# Schematic.net
KiCad netlist of a schematic drawn in Altium Designer
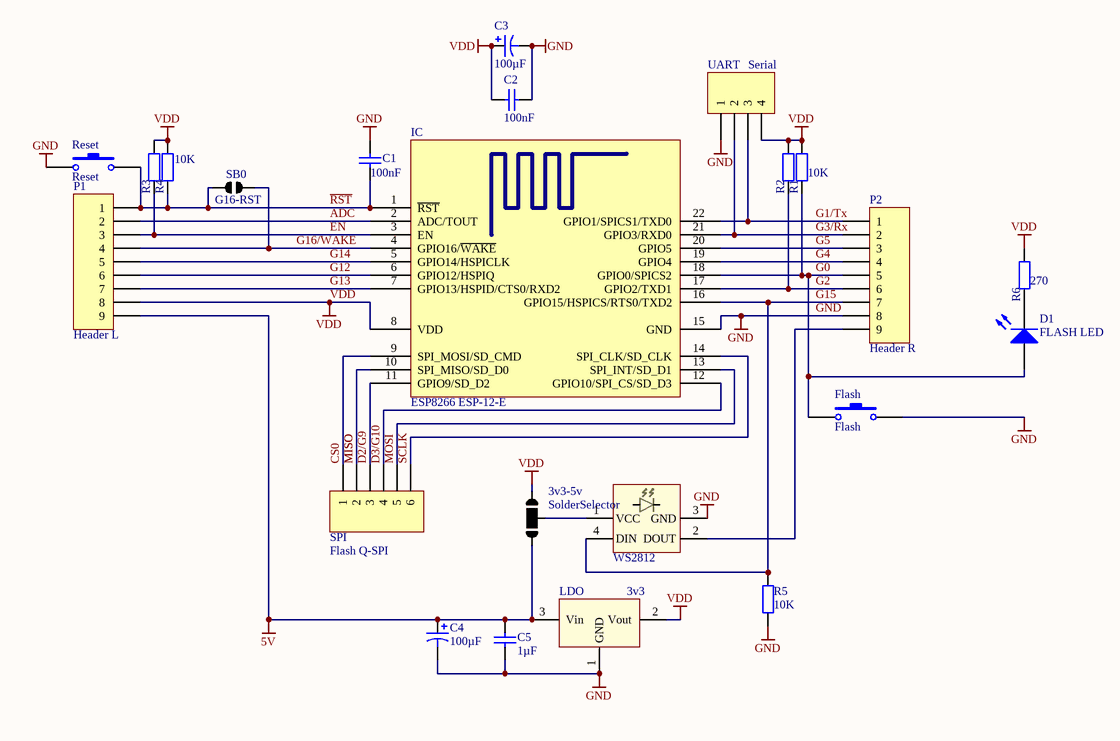
[diagram p0: Schematic.SchDoc]

(export (version "E")
  (design (tool "Eeschema 10.0.6"))
  (components
    (comp (ref "3v3-5v")
      (value "SolderSelector")
      (footprint "SolderSelector")
      (libsource (lib "Misc") (part "SolderSelector"))
    )
    (comp (ref "C1")
      (value "100nF")
      (footprint "C1206")
      (description "Capacitor (Semiconductor SIM Model)")
      (fields (field (name "Comment") "Cap Semi") (field (name "PUBLISHER") "Altium Limited"))
      (libsource (lib "Miscellaneous Devices") (part "Cap Semi"))
    )
    (comp (ref "C2")
      (value "100nF")
      (footprint "C1206")
      (description "Capacitor (Semiconductor SIM Model)")
      (fields (field (name "Comment") "Cap Semi") (field (name "PUBLISHER") "Altium Limited"))
      (libsource (lib "Miscellaneous Devices") (part "Cap Semi"))
    )
    (comp (ref "C3")
      (value "100µF")
      (footprint "SMD cap 6x5")
      (description "Polarized Capacitor (Radial)")
      (fields (field (name "PUBLISHER") "Altium Limited"))
      (libsource (lib "Miscellaneous Devices") (part "Cap Pol1"))
    )
    (comp (ref "C4")
      (value "100µF")
      (footprint "SMD cap 6x5")
      (description "Polarized Capacitor (Radial)")
      (fields (field (name "PUBLISHER") "Altium Limited"))
      (libsource (lib "Miscellaneous Devices") (part "Cap Pol1"))
    )
    (comp (ref "C5")
      (value "1µF")
      (footprint "C1206")
      (description "Capacitor")
      (fields (field (name "PUBLISHER") "Altium Limited"))
      (libsource (lib "Miscellaneous Devices") (part "Cap"))
    )
    (comp (ref "D1")
      (value "FLASH LED")
      (footprint "C1206")
      (description "Typical RED, GREEN, YELLOW, AMBER GaAs LED")
      (fields (field (name "PUBLISHER") "Altium Limited"))
      (libsource (lib "Miscellaneous Devices") (part "LED2"))
    )
    (comp (ref "Flash")
      (value "Flash")
      (footprint "SMDswitch")
      (description "Switch")
      (fields (field (name "PUBLISHER") "Altium Limited"))
      (libsource (lib "Miscellaneous Devices") (part "SW-PB"))
    )
    (comp (ref "IC")
      (value "ESP8266 ESP-12-E")
      (footprint "ESP8266 ESP-12-E")
      (libsource (lib "ESP8266") (part "ESP8266 ESP-12-E"))
    )
    (comp (ref "LDO")
      (value "3v3")
      (footprint "SOT-23A")
      (description "Power regulator")
      (libsource (lib "Project2") (part "MCP1703"))
    )
    (comp (ref "P1")
      (value "Header L")
      (footprint "HDR1X9")
      (description "Header, 9-Pin")
      (fields (field (name "PUBLISHER") "Altium Limited"))
      (libsource (lib "") (part "Header 9_1"))
    )
    (comp (ref "P2")
      (value "Header R")
      (footprint "HDR1X9")
      (description "Header, 9-Pin")
      (fields (field (name "PUBLISHER") "Altium Limited"))
      (libsource (lib "Miscellaneous Connectors") (part "Header 9"))
    )
    (comp (ref "R1")
      (value "10K")
      (footprint "C1206")
      (description "Resistor")
      (fields (field (name "Comment") "Res2") (field (name "PUBLISHER") "Altium Limited"))
      (libsource (lib "Miscellaneous Devices") (part "Res2"))
    )
    (comp (ref "R2")
      (value "Res2")
      (footprint "C1206")
      (description "Resistor")
      (fields (field (name "PUBLISHER") "Altium Limited"))
      (libsource (lib "Miscellaneous Devices") (part "Res2"))
    )
    (comp (ref "R3")
      (value "10K")
      (footprint "C1206")
      (description "Resistor")
      (fields (field (name "Comment") "Res2") (field (name "PUBLISHER") "Altium Limited"))
      (libsource (lib "Miscellaneous Devices") (part "Res2"))
    )
    (comp (ref "R4")
      (value "Res2")
      (footprint "C1206")
      (description "Resistor")
      (fields (field (name "PUBLISHER") "Altium Limited"))
      (libsource (lib "Miscellaneous Devices") (part "Res2"))
    )
    (comp (ref "R5")
      (value "10K")
      (footprint "C1206")
      (description "Resistor")
      (fields (field (name "Comment") "Res2") (field (name "PUBLISHER") "Altium Limited"))
      (libsource (lib "Miscellaneous Devices") (part "Res2"))
    )
    (comp (ref "R6")
      (value "270")
      (footprint "C1206")
      (description "Resistor")
      (fields (field (name "Comment") "Res2") (field (name "PUBLISHER") "Altium Limited"))
      (libsource (lib "Miscellaneous Devices") (part "Res2"))
    )
    (comp (ref "Reset")
      (value "Reset")
      (footprint "SMDswitch")
      (description "Switch")
      (fields (field (name "PUBLISHER") "Altium Limited"))
      (libsource (lib "Miscellaneous Devices") (part "SW-PB"))
    )
    (comp (ref "SB0")
      (value "G16-RST")
      (footprint "SolderBridge")
      (libsource (lib "Misc") (part "SolderBridge"))
    )
    (comp (ref "SPI")
      (value "Flash Q-SPI")
      (footprint "HDR1X6")
      (description "Header, 6-Pin")
      (fields (field (name "PUBLISHER") "Altium Limited"))
      (libsource (lib "Miscellaneous Connectors") (part "Header 6"))
    )
    (comp (ref "UART")
      (value "Serial")
      (footprint "HDR1X4")
      (description "Header, 4-Pin")
      (fields (field (name "PUBLISHER") "Altium Limited"))
      (libsource (lib "Miscellaneous Connectors") (part "Header 4"))
    )
    (comp (ref "WS2812")
      (value "WS2812")
      (footprint "WS2812B")
      (description "Serial RGB Led")
      (libsource (lib "Project2") (part "WS2812"))
    )
  )
  (nets
    (net (code "1") (name "/ADC") (class "Default")
      (node (ref "IC") (pin "2") (pinfunction "ADC/TOUT_2") (pintype "passive"))
      (node (ref "P1") (pin "2") (pinfunction "2_2") (pintype "passive"))
    )
    (net (code "2") (name "/CS0") (class "Default")
      (node (ref "IC") (pin "9") (pinfunction "SPI_MOSI/SD_CMD_9") (pintype "passive"))
      (node (ref "SPI") (pin "1") (pinfunction "1_1") (pintype "passive"))
    )
    (net (code "3") (name "/D2{slash}G9") (class "Default")
      (node (ref "IC") (pin "11") (pinfunction "GPIO9/SD_D2_11") (pintype "passive"))
      (node (ref "SPI") (pin "3") (pinfunction "3_3") (pintype "passive"))
    )
    (net (code "4") (name "/D3{slash}G10") (class "Default")
      (node (ref "IC") (pin "12") (pinfunction "GPIO10/SPI_CS/SD_D3_12") (pintype "passive"))
      (node (ref "SPI") (pin "4") (pinfunction "4_4") (pintype "passive"))
    )
    (net (code "5") (name "/EN") (class "Default")
      (node (ref "IC") (pin "3") (pinfunction "EN_3") (pintype "passive"))
      (node (ref "P1") (pin "3") (pinfunction "3_3") (pintype "passive"))
      (node (ref "R3") (pin "1") (pinfunction "1_1") (pintype "passive"))
    )
    (net (code "6") (name "/G0") (class "Default")
      (node (ref "D1") (pin "1") (pinfunction "A_1") (pintype "passive"))
      (node (ref "Flash") (pin "1") (pinfunction "1_1") (pintype "passive"))
      (node (ref "IC") (pin "18") (pinfunction "GPIO0/SPICS2_18") (pintype "passive"))
      (node (ref "P2") (pin "5") (pinfunction "5_5") (pintype "passive"))
      (node (ref "R1") (pin "1") (pinfunction "1_1") (pintype "passive"))
    )
    (net (code "7") (name "/G1{slash}Tx") (class "Default")
      (node (ref "IC") (pin "22") (pinfunction "GPIO1/SPICS1/TXD0_22") (pintype "passive"))
      (node (ref "P2") (pin "1") (pinfunction "1_1") (pintype "passive"))
      (node (ref "UART") (pin "3") (pinfunction "3_3") (pintype "passive"))
    )
    (net (code "8") (name "/G2") (class "Default")
      (node (ref "IC") (pin "17") (pinfunction "GPIO2/TXD1_17") (pintype "passive"))
      (node (ref "P2") (pin "6") (pinfunction "6_6") (pintype "passive"))
      (node (ref "R2") (pin "1") (pinfunction "1_1") (pintype "passive"))
    )
    (net (code "9") (name "/G3{slash}Rx") (class "Default")
      (node (ref "IC") (pin "21") (pinfunction "GPIO3/RXD0_21") (pintype "passive"))
      (node (ref "P2") (pin "2") (pinfunction "2_2") (pintype "passive"))
      (node (ref "UART") (pin "2") (pinfunction "2_2") (pintype "passive"))
    )
    (net (code "10") (name "/G4") (class "Default")
      (node (ref "IC") (pin "19") (pinfunction "GPIO4_19") (pintype "passive"))
      (node (ref "P2") (pin "4") (pinfunction "4_4") (pintype "passive"))
    )
    (net (code "11") (name "/G5") (class "Default")
      (node (ref "IC") (pin "20") (pinfunction "GPIO5_20") (pintype "passive"))
      (node (ref "P2") (pin "3") (pinfunction "3_3") (pintype "passive"))
    )
    (net (code "12") (name "/G12") (class "Default")
      (node (ref "IC") (pin "6") (pinfunction "GPIO12/HSPIQ_6") (pintype "passive"))
      (node (ref "P1") (pin "6") (pinfunction "6_6") (pintype "passive"))
    )
    (net (code "13") (name "/G13") (class "Default")
      (node (ref "IC") (pin "7") (pinfunction "GPIO13/HSPID/CTS0/RXD2_7") (pintype "passive"))
      (node (ref "P1") (pin "7") (pinfunction "7_7") (pintype "passive"))
    )
    (net (code "14") (name "/G14") (class "Default")
      (node (ref "IC") (pin "5") (pinfunction "GPIO14/HSPICLK_5") (pintype "passive"))
      (node (ref "P1") (pin "5") (pinfunction "5_5") (pintype "passive"))
    )
    (net (code "15") (name "/G15") (class "Default")
      (node (ref "IC") (pin "16") (pinfunction "GPIO15/HSPICS/RTS0/TXD2_16") (pintype "passive"))
      (node (ref "P2") (pin "7") (pinfunction "7_7") (pintype "passive"))
      (node (ref "R5") (pin "2") (pinfunction "2_2") (pintype "passive"))
      (node (ref "WS2812") (pin "4") (pinfunction "DIN_4") (pintype "passive"))
    )
    (net (code "16") (name "/G16{slash}~{WAKE}") (class "Default")
      (node (ref "IC") (pin "4") (pinfunction "GPIO16/~{WAKE}_4") (pintype "passive"))
      (node (ref "P1") (pin "4") (pinfunction "4_4") (pintype "passive"))
      (node (ref "SB0") (pin "1") (pintype "passive"))
    )
    (net (code "17") (name "/MISO") (class "Default")
      (node (ref "IC") (pin "10") (pinfunction "SPI_MISO/SD_D0_10") (pintype "passive"))
      (node (ref "SPI") (pin "2") (pinfunction "2_2") (pintype "passive"))
    )
    (net (code "18") (name "/MOSI") (class "Default")
      (node (ref "IC") (pin "13") (pinfunction "SPI_INT/SD_D1_13") (pintype "passive"))
      (node (ref "SPI") (pin "5") (pinfunction "5_5") (pintype "passive"))
    )
    (net (code "19") (name "/SCLK") (class "Default")
      (node (ref "IC") (pin "14") (pinfunction "SPI_CLK/SD_CLK_14") (pintype "passive"))
      (node (ref "SPI") (pin "6") (pinfunction "6_6") (pintype "passive"))
    )
    (net (code "20") (name "/~{RST}") (class "Default")
      (node (ref "C1") (pin "1") (pinfunction "1_1") (pintype "passive"))
      (node (ref "IC") (pin "1") (pinfunction "~{RST}_1") (pintype "passive"))
      (node (ref "P1") (pin "1") (pinfunction "1_1") (pintype "passive"))
      (node (ref "R4") (pin "1") (pinfunction "1_1") (pintype "passive"))
      (node (ref "Reset") (pin "2") (pinfunction "2_2") (pintype "passive"))
      (node (ref "SB0") (pin "0") (pintype "passive"))
    )
    (net (code "21") (name "5V") (class "Default")
      (node (ref "3v3-5v") (pin "1") (pintype "passive"))
      (node (ref "C4") (pin "1") (pinfunction "1_1") (pintype "passive"))
      (node (ref "C5") (pin "2") (pinfunction "2_2") (pintype "passive"))
      (node (ref "LDO") (pin "3") (pinfunction "Vin_3") (pintype "power_in"))
      (node (ref "P1") (pin "9") (pinfunction "9_9") (pintype "passive"))
    )
    (net (code "22") (name "GND") (class "Default")
      (node (ref "C1") (pin "2") (pinfunction "2_2") (pintype "passive"))
      (node (ref "C2") (pin "2") (pinfunction "2_2") (pintype "passive"))
      (node (ref "C3") (pin "2") (pinfunction "2_2") (pintype "passive"))
      (node (ref "C4") (pin "2") (pinfunction "2_2") (pintype "passive"))
      (node (ref "C5") (pin "1") (pinfunction "1_1") (pintype "passive"))
      (node (ref "Flash") (pin "2") (pinfunction "2_2") (pintype "passive"))
      (node (ref "IC") (pin "15") (pinfunction "GND_15") (pintype "passive"))
      (node (ref "LDO") (pin "1") (pinfunction "GND_1") (pintype "power_in"))
      (node (ref "P2") (pin "8") (pinfunction "8_8") (pintype "passive"))
      (node (ref "R5") (pin "1") (pinfunction "1_1") (pintype "passive"))
      (node (ref "Reset") (pin "1") (pinfunction "1_1") (pintype "passive"))
      (node (ref "UART") (pin "1") (pinfunction "1_1") (pintype "passive"))
      (node (ref "WS2812") (pin "3") (pinfunction "GND_3") (pintype "power_in"))
    )
    (net (code "23") (name "Net-(D1-K)") (class "Default")
      (node (ref "D1") (pin "2") (pinfunction "K_2") (pintype "passive"))
      (node (ref "R6") (pin "1") (pinfunction "1_1") (pintype "passive"))
    )
    (net (code "24") (name "Net-(WS2812-DOUT)") (class "Default")
      (node (ref "P2") (pin "9") (pinfunction "9_9") (pintype "passive"))
      (node (ref "WS2812") (pin "2") (pinfunction "DOUT_2") (pintype "passive"))
    )
    (net (code "25") (name "Net-(WS2812-VCC)") (class "Default")
      (node (ref "3v3-5v") (pin "2") (pinfunction "2_2") (pintype "passive"))
      (node (ref "WS2812") (pin "1") (pinfunction "VCC_1") (pintype "power_in"))
    )
    (net (code "26") (name "VDD") (class "Default")
      (node (ref "3v3-5v") (pin "0") (pintype "passive"))
      (node (ref "C2") (pin "1") (pinfunction "1_1") (pintype "passive"))
      (node (ref "C3") (pin "1") (pinfunction "1_1") (pintype "passive"))
      (node (ref "IC") (pin "8") (pinfunction "VDD_8") (pintype "passive"))
      (node (ref "LDO") (pin "2") (pinfunction "Vout_2") (pintype "power_in"))
      (node (ref "P1") (pin "8") (pinfunction "8_8") (pintype "passive"))
      (node (ref "R1") (pin "2") (pinfunction "2_2") (pintype "passive"))
      (node (ref "R2") (pin "2") (pinfunction "2_2") (pintype "passive"))
      (node (ref "R3") (pin "2") (pinfunction "2_2") (pintype "passive"))
      (node (ref "R4") (pin "2") (pinfunction "2_2") (pintype "passive"))
      (node (ref "R6") (pin "2") (pinfunction "2_2") (pintype "passive"))
      (node (ref "UART") (pin "4") (pinfunction "4_4") (pintype "passive"))
    )
  )
)
